# 5V_TO_3V_VD.net
KiCad netlist of a schematic drawn in Altium Designer
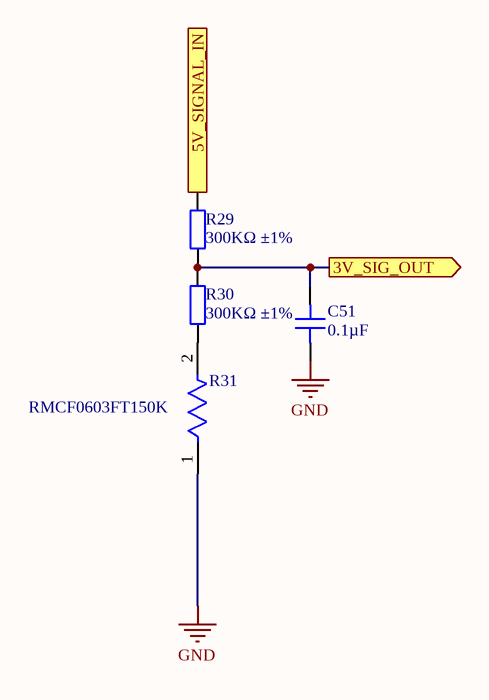
[diagram p0: 5V_TO_3V_VD.SchDoc]

(export (version "E")
  (design (tool "Eeschema 10.0.6"))
  (components
    (comp (ref "C51")
      (value "0.1µF")
      (footprint "CAP 0402_1005")
      (description "CAP CER 0402 0.1UF 16V X7R 10%")
      (fields (field (name "PART NUMBER") "C0402C104K4RECAUTO") (field (name "MANUFACTURER") "KEMET"))
      (libsource (lib "CAL") (part "Capacitor"))
    )
    (comp (ref "R29")
      (value "300KΩ ±1%")
      (footprint "0402_R")
      (description "Chip resistor")
      (fields (field (name "MANUFACTURER") "Uniroyal Elec") (field (name "PARTNUMBER") "0402WGF3003TCE"))
      (libsource (lib "Miscellaneous Devices LC") (part "0402 300K (3003) 1%"))
    )
    (comp (ref "R30")
      (value "300KΩ ±1%")
      (footprint "0402_R")
      (description "Chip resistor")
      (fields (field (name "MANUFACTURER") "Uniroyal Elec") (field (name "PARTNUMBER") "0402WGF3003TCE"))
      (libsource (lib "Miscellaneous Devices LC") (part "0402 300K (3003) 1%"))
    )
    (comp (ref "R31")
      (value "RMCF0603FT150K")
      (footprint "FP-RMCF0603-IPC_B")
      (description "150kΩ ±1% 0.1W 0603 Thick Film Chip Resistor AEC-Q200 compliant")
      (fields (field (name "TOLERANCE") "1%"))
      (libsource (lib "Altium Content Vault") (part "1029c3af85768c4190bb7ad29bc67b5"))
    )
  )
  (nets
    (net (code "1") (name "/3V_SIG_OUT") (class "Default")
      (node (ref "C51") (pin "1") (pinfunction "1_1") (pintype "passive"))
      (node (ref "R29") (pin "1") (pinfunction "1_1") (pintype "passive"))
      (node (ref "R30") (pin "2") (pinfunction "2_2") (pintype "passive"))
    )
    (net (code "2") (name "/5V_SIGNAL_IN") (class "Default")
      (node (ref "R29") (pin "2") (pinfunction "2_2") (pintype "passive"))
    )
    (net (code "3") (name "GND") (class "Default")
      (node (ref "C51") (pin "2") (pinfunction "2_2") (pintype "passive"))
      (node (ref "R31") (pin "1") (pinfunction "1_1") (pintype "passive"))
    )
    (net (code "4") (name "Net-(R30-Pad1)") (class "Default")
      (node (ref "R30") (pin "1") (pinfunction "1_1") (pintype "passive"))
      (node (ref "R31") (pin "2") (pinfunction "2_2") (pintype "passive"))
    )
  )
)
